# SystemStatusBoard.net
KiCad netlist of a schematic drawn in Altium Designer
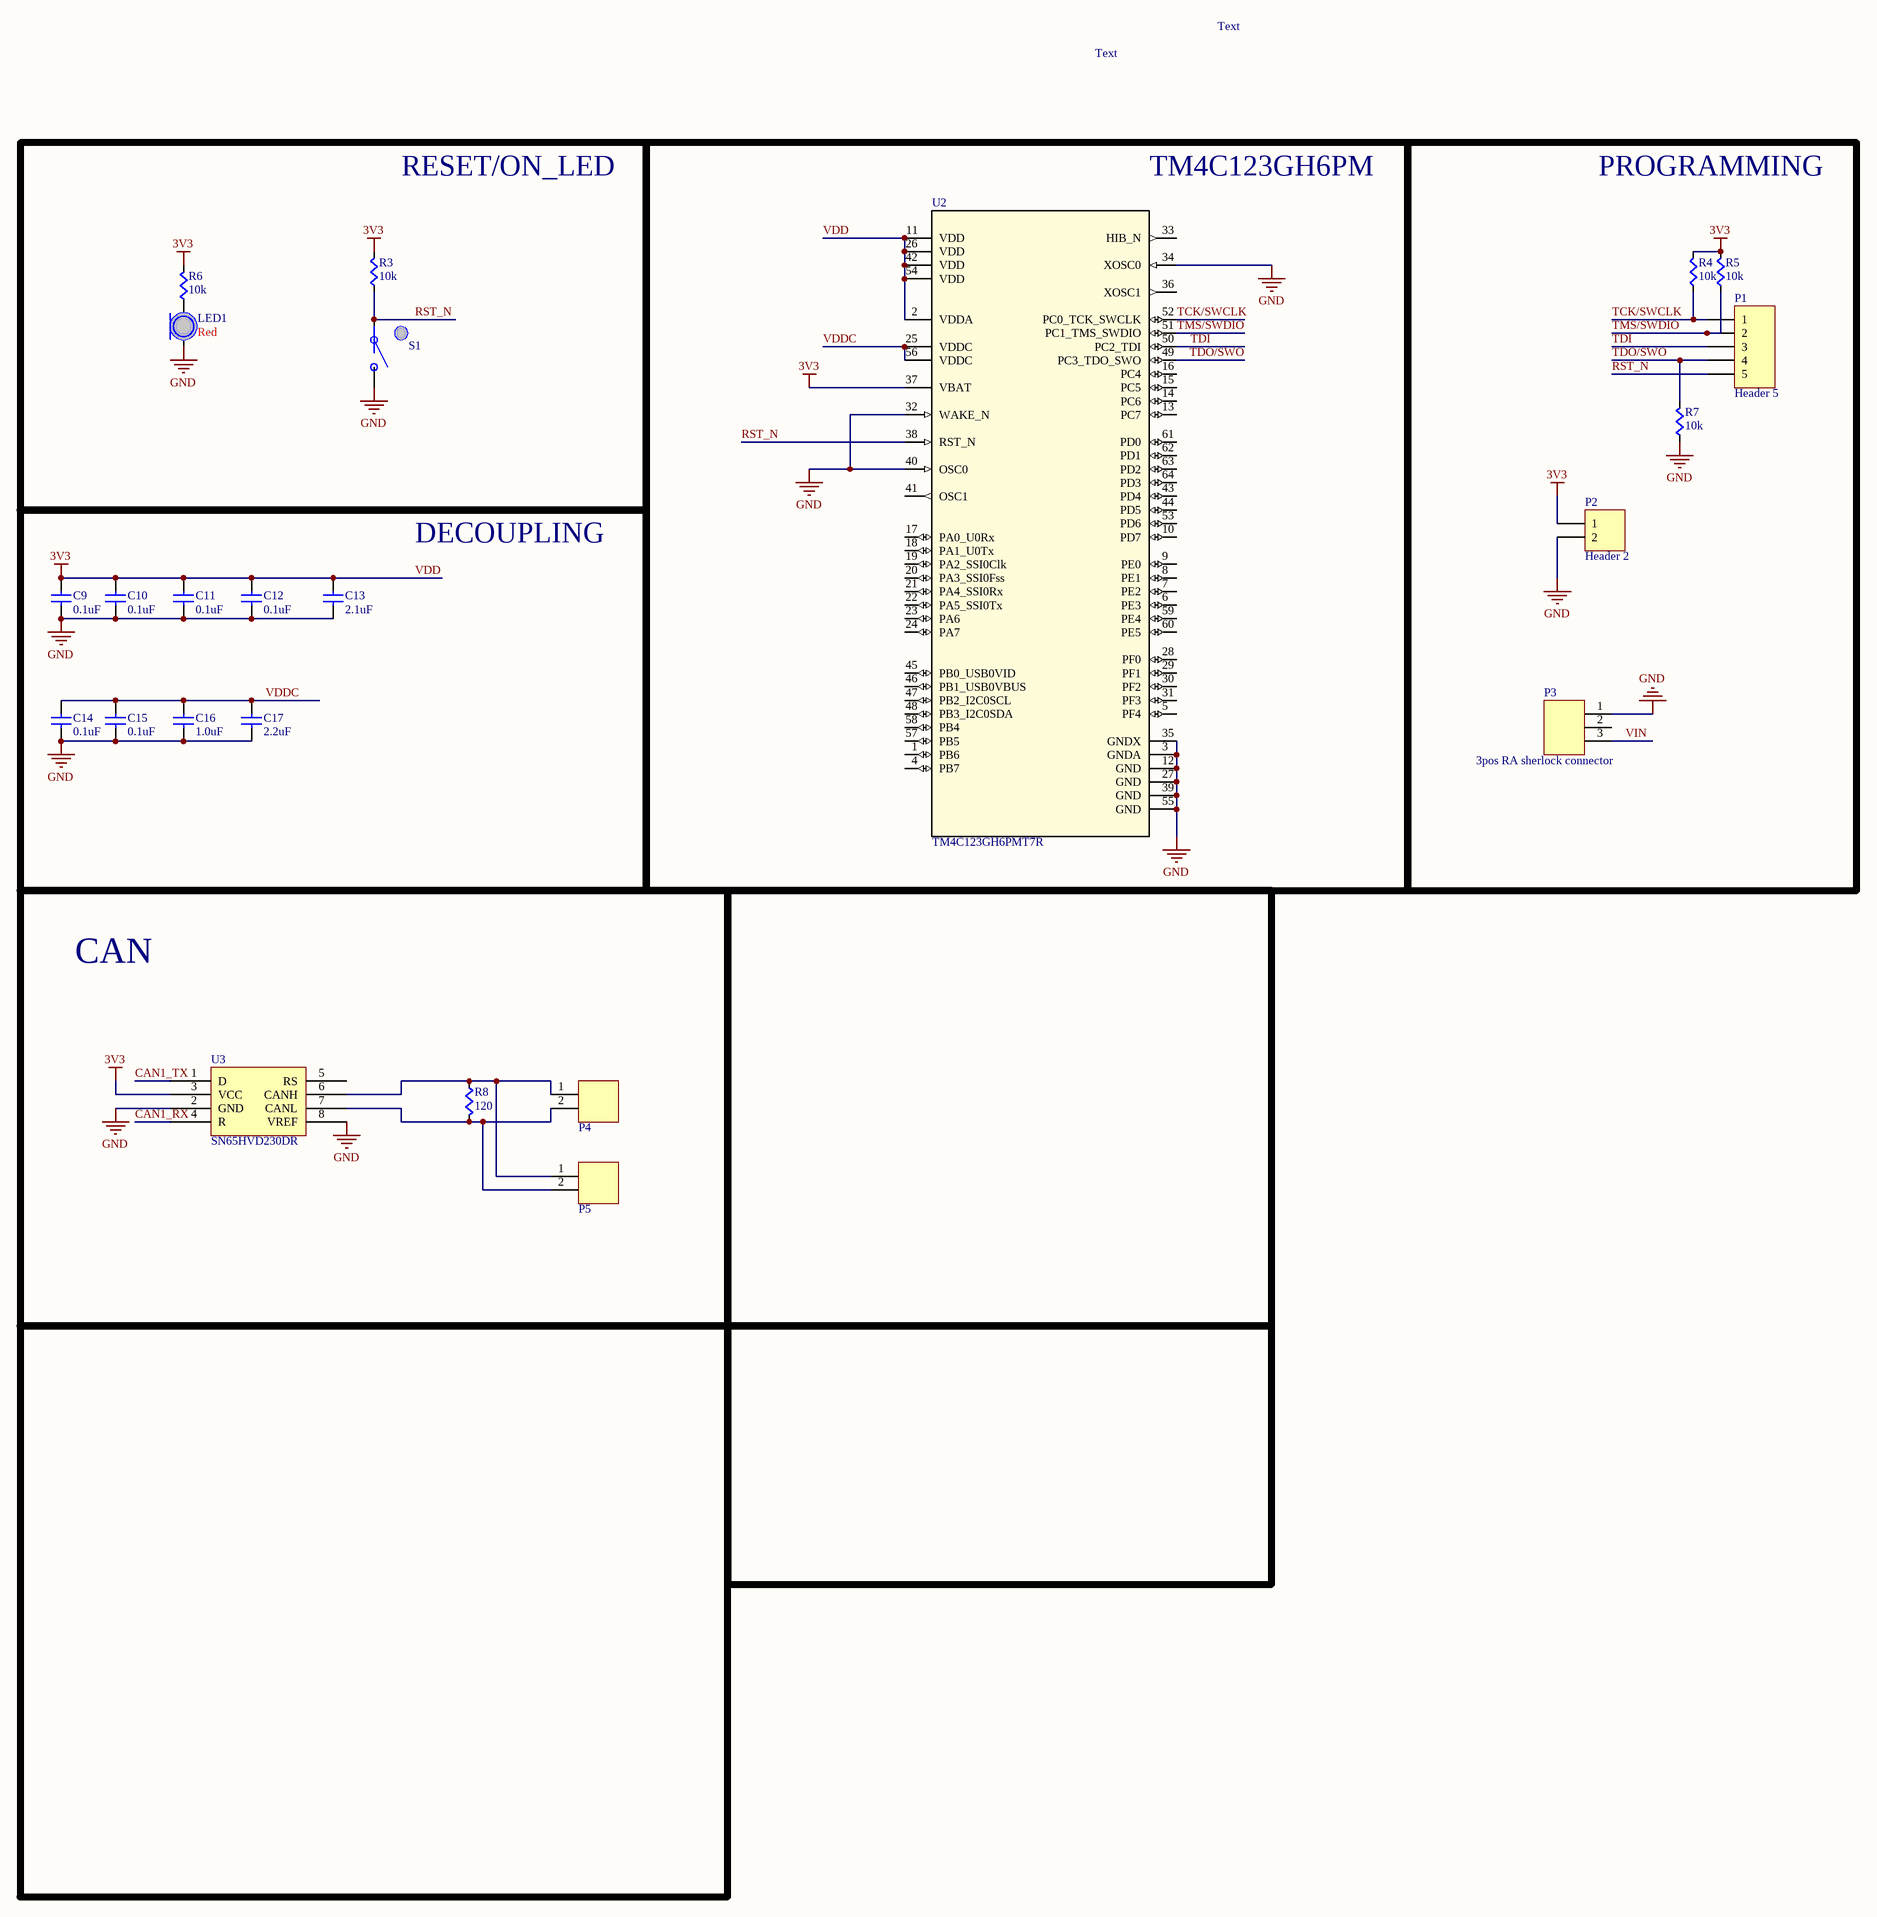
[diagram p0: SystemStatusBoard.SchDoc]

(export (version "E")
  (design (tool "Eeschema 10.0.6"))
  (components
    (comp (ref "C9")
      (value "0.1uF")
      (footprint "CAPC0603")
      (fields (field (name "Comment") "Cap"))
      (libsource (lib "SubjuGator8") (part "Cap"))
    )
    (comp (ref "C10")
      (value "0.1uF")
      (footprint "CAPC0603")
      (fields (field (name "Comment") "Cap"))
      (libsource (lib "SubjuGator8") (part "Cap"))
    )
    (comp (ref "C11")
      (value "0.1uF")
      (footprint "CAPC0603")
      (fields (field (name "Comment") "Cap"))
      (libsource (lib "SubjuGator8") (part "Cap"))
    )
    (comp (ref "C12")
      (value "0.1uF")
      (footprint "CAPC0603")
      (fields (field (name "Comment") "Cap"))
      (libsource (lib "SubjuGator8") (part "Cap"))
    )
    (comp (ref "C13")
      (value "2.1uF")
      (footprint "CAPC0603")
      (fields (field (name "Comment") "Cap"))
      (libsource (lib "SubjuGator8") (part "Cap"))
    )
    (comp (ref "C14")
      (value "0.1uF")
      (footprint "CAPC0603")
      (fields (field (name "Comment") "Cap"))
      (libsource (lib "SubjuGator8") (part "Cap"))
    )
    (comp (ref "C15")
      (value "0.1uF")
      (footprint "CAPC0603")
      (fields (field (name "Comment") "Cap"))
      (libsource (lib "SubjuGator8") (part "Cap"))
    )
    (comp (ref "C16")
      (value "1.0uF")
      (footprint "CAPC0603")
      (fields (field (name "Comment") "Cap"))
      (libsource (lib "SubjuGator8") (part "Cap"))
    )
    (comp (ref "C17")
      (value "2.2uF")
      (footprint "CAPC0603")
      (fields (field (name "Comment") "Cap"))
      (libsource (lib "SubjuGator8") (part "Cap"))
    )
    (comp (ref "LED1")
      (value "LED")
      (footprint "LED0603")
      (fields (field (name "COLOR") "Red"))
      (libsource (lib "SubjuGator8") (part "LED"))
    )
    (comp (ref "P1")
      (value "Header 5")
      (footprint "HDR1X5")
      (description "Header, 5-Pin")
      (fields (field (name "PUBLISHER") "Altium Limited"))
      (libsource (lib "Miscellaneous Connectors") (part "Header 5"))
    )
    (comp (ref "P2")
      (value "Header 2")
      (footprint "HDR1X2")
      (description "Header, 2-Pin")
      (fields (field (name "PUBLISHER") "Altium Limited"))
      (libsource (lib "Miscellaneous Connectors") (part "Header 2"))
    )
    (comp (ref "P3")
      (value "3pos RA sherlock connector")
      (footprint "MOLEX-HDR-1X3-SHERLOCK-RA")
      (description "Header, Molex, 2mm Pitch Sherlock Header, Single Row, Right Angle 3 Circuits, Length 3.3mm")
      (fields
        (field (name "MANUFACTURER PART NUMBER") "35363-0360")
        (field (name "MANUFACTURER") "Molex Connector Corporation")
      )
      (libsource (lib "Connectors") (part "MOLEX-HDR-1x3-SHERLOCK_RA"))
    )
    (comp (ref "P4")
      (value "2-pin Horz Sherlock")
      (footprint "MOLEX-HDR-1X2-SHERLOCK-HORZ")
      (fields
        (field (name "MANUFACTURER PART NUMBER") "0353630260")
        (field (name "MANUFACTURER") "Molex Inc")
      )
      (libsource (lib "SubjuGator8") (part "MOLEX-HDR-1x2-SHERLOCK_RA"))
    )
    (comp (ref "P5")
      (value "2-pin Horz Sherlock")
      (footprint "MOLEX-HDR-1X2-SHERLOCK-HORZ")
      (fields
        (field (name "MANUFACTURER PART NUMBER") "0353630260")
        (field (name "MANUFACTURER") "Molex Inc")
      )
      (libsource (lib "SubjuGator8") (part "MOLEX-HDR-1x2-SHERLOCK_RA"))
    )
    (comp (ref "R3")
      (value "10k")
      (footprint "RES0603")
      (fields (field (name "Comment") "Res"))
      (libsource (lib "SubjuGator8") (part "Res"))
    )
    (comp (ref "R4")
      (value "10k")
      (footprint "RES0603")
      (fields (field (name "Comment") "Res"))
      (libsource (lib "SubjuGator8") (part "Res"))
    )
    (comp (ref "R5")
      (value "10k")
      (footprint "RES0603")
      (fields (field (name "Comment") "Res"))
      (libsource (lib "SubjuGator8") (part "Res"))
    )
    (comp (ref "R6")
      (value "10k")
      (footprint "RES0603")
      (fields (field (name "Comment") "Res"))
      (libsource (lib "SubjuGator8") (part "Res"))
    )
    (comp (ref "R7")
      (value "10k")
      (footprint "RES0603")
      (fields (field (name "Comment") "Res"))
      (libsource (lib "SubjuGator8") (part "Res"))
    )
    (comp (ref "R8")
      (value "120")
      (footprint "RES0603")
      (fields (field (name "Comment") "Res"))
      (libsource (lib "SubjuGator8") (part "Res"))
    )
    (comp (ref "S1")
      (value "Button")
      (footprint "PTS645xxxxSMTR92")
      (description "SPST Button")
      (libsource (lib "SubjuGator8") (part "Button"))
    )
    (comp (ref "U2")
      (value "TM4C123GH6PMT7R")
      (footprint "PM0064A_N")
      (description "Imported")
      (fields
        (field (name "PARTNUMBER") "TM4C123GH6PMTR")
        (field (name "ALTERNATE_PARTNUMBER") "TM4C123GH6PMT")
      )
      (libsource (lib "TivaC") (part "TM4C123GH6PMT7R"))
    )
    (comp (ref "U3")
      (value "SN65HVD230DR")
      (footprint "SOIC-8pin")
      (description "IC TXRX CAN 1MBPS 3.3V 8SOIC")
      (libsource (lib "SubjuGator8") (part "SN65HVD230DR"))
    )
  )
  (nets
    (net (code "1") (name "/CAN1_RX") (class "Default")
      (node (ref "U3") (pin "4") (pinfunction "R_4") (pintype "passive"))
    )
    (net (code "2") (name "/CAN1_TX") (class "Default")
      (node (ref "U3") (pin "1") (pinfunction "D_1") (pintype "passive"))
    )
    (net (code "3") (name "/RST_N") (class "Default")
      (node (ref "P1") (pin "5") (pinfunction "5_5") (pintype "passive"))
      (node (ref "R3") (pin "2") (pinfunction "B_2") (pintype "passive"))
      (node (ref "S1") (pin "A") (pinfunction "A_A") (pintype "passive"))
      (node (ref "U2") (pin "38") (pinfunction "RST_N_38") (pintype "input"))
    )
    (net (code "4") (name "/TCK{slash}SWCLK") (class "Default")
      (node (ref "P1") (pin "1") (pinfunction "1_1") (pintype "passive"))
      (node (ref "R4") (pin "2") (pinfunction "B_2") (pintype "passive"))
      (node (ref "U2") (pin "52") (pinfunction "PC0_TCK_SWCLK_52") (pintype "bidirectional"))
    )
    (net (code "5") (name "/TDI") (class "Default")
      (node (ref "P1") (pin "3") (pinfunction "3_3") (pintype "passive"))
      (node (ref "U2") (pin "50") (pinfunction "PC2_TDI_50") (pintype "bidirectional"))
    )
    (net (code "6") (name "/TDO{slash}SWO") (class "Default")
      (node (ref "P1") (pin "4") (pinfunction "4_4") (pintype "passive"))
      (node (ref "R7") (pin "1") (pinfunction "A_1") (pintype "passive"))
      (node (ref "U2") (pin "49") (pinfunction "PC3_TDO_SWO_49") (pintype "bidirectional"))
    )
    (net (code "7") (name "/TMS{slash}SWDIO") (class "Default")
      (node (ref "P1") (pin "2") (pinfunction "2_2") (pintype "passive"))
      (node (ref "R5") (pin "2") (pinfunction "B_2") (pintype "passive"))
      (node (ref "U2") (pin "51") (pinfunction "PC1_TMS_SWDIO_51") (pintype "bidirectional"))
    )
    (net (code "8") (name "/VDDC") (class "Default")
      (node (ref "C14") (pin "1") (pinfunction "A_1") (pintype "passive"))
      (node (ref "C15") (pin "1") (pinfunction "A_1") (pintype "passive"))
      (node (ref "C16") (pin "1") (pinfunction "A_1") (pintype "passive"))
      (node (ref "C17") (pin "1") (pinfunction "A_1") (pintype "passive"))
      (node (ref "U2") (pin "25") (pinfunction "VDDC_25") (pintype "power_in"))
      (node (ref "U2") (pin "56") (pinfunction "VDDC_56") (pintype "power_in"))
    )
    (net (code "9") (name "/VIN") (class "Default")
      (node (ref "P3") (pin "3") (pinfunction "3_3") (pintype "passive"))
    )
    (net (code "10") (name "3V3") (class "Default")
      (node (ref "C10") (pin "1") (pinfunction "A_1") (pintype "passive"))
      (node (ref "C11") (pin "1") (pinfunction "A_1") (pintype "passive"))
      (node (ref "C12") (pin "1") (pinfunction "A_1") (pintype "passive"))
      (node (ref "C13") (pin "1") (pinfunction "A_1") (pintype "passive"))
      (node (ref "C9") (pin "1") (pinfunction "A_1") (pintype "passive"))
      (node (ref "P2") (pin "1") (pinfunction "1_1") (pintype "passive"))
      (node (ref "R3") (pin "1") (pinfunction "A_1") (pintype "passive"))
      (node (ref "R4") (pin "1") (pinfunction "A_1") (pintype "passive"))
      (node (ref "R5") (pin "1") (pinfunction "A_1") (pintype "passive"))
      (node (ref "R6") (pin "1") (pinfunction "A_1") (pintype "passive"))
      (node (ref "U2") (pin "11") (pinfunction "VDD_11") (pintype "power_in"))
      (node (ref "U2") (pin "2") (pinfunction "VDDA_2") (pintype "power_in"))
      (node (ref "U2") (pin "26") (pinfunction "VDD_26") (pintype "power_in"))
      (node (ref "U2") (pin "37") (pinfunction "VBAT_37") (pintype "power_in"))
      (node (ref "U2") (pin "42") (pinfunction "VDD_42") (pintype "power_in"))
      (node (ref "U2") (pin "54") (pinfunction "VDD_54") (pintype "power_in"))
      (node (ref "U3") (pin "3") (pinfunction "VCC_3") (pintype "passive"))
    )
    (net (code "11") (name "GND") (class "Default")
      (node (ref "C10") (pin "2") (pinfunction "B_2") (pintype "passive"))
      (node (ref "C11") (pin "2") (pinfunction "B_2") (pintype "passive"))
      (node (ref "C12") (pin "2") (pinfunction "B_2") (pintype "passive"))
      (node (ref "C13") (pin "2") (pinfunction "B_2") (pintype "passive"))
      (node (ref "C14") (pin "2") (pinfunction "B_2") (pintype "passive"))
      (node (ref "C15") (pin "2") (pinfunction "B_2") (pintype "passive"))
      (node (ref "C16") (pin "2") (pinfunction "B_2") (pintype "passive"))
      (node (ref "C17") (pin "2") (pinfunction "B_2") (pintype "passive"))
      (node (ref "C9") (pin "2") (pinfunction "B_2") (pintype "passive"))
      (node (ref "LED1") (pin "C") (pinfunction "C_C") (pintype "passive"))
      (node (ref "P2") (pin "2") (pinfunction "2_2") (pintype "passive"))
      (node (ref "P3") (pin "1") (pinfunction "1_1") (pintype "passive"))
      (node (ref "R7") (pin "2") (pinfunction "B_2") (pintype "passive"))
      (node (ref "S1") (pin "B") (pinfunction "B_B") (pintype "passive"))
      (node (ref "U2") (pin "12") (pinfunction "GND_12") (pintype "power_in"))
      (node (ref "U2") (pin "27") (pinfunction "GND_27") (pintype "power_in"))
      (node (ref "U2") (pin "3") (pinfunction "GNDA_3") (pintype "power_in"))
      (node (ref "U2") (pin "32") (pinfunction "WAKE_N_32") (pintype "input"))
      (node (ref "U2") (pin "34") (pinfunction "XOSC0_34") (pintype "input"))
      (node (ref "U2") (pin "35") (pinfunction "GNDX_35") (pintype "power_in"))
      (node (ref "U2") (pin "39") (pinfunction "GND_39") (pintype "power_in"))
      (node (ref "U2") (pin "40") (pinfunction "OSC0_40") (pintype "input"))
      (node (ref "U2") (pin "55") (pinfunction "GND_55") (pintype "power_in"))
      (node (ref "U3") (pin "2") (pinfunction "GND_2") (pintype "passive"))
      (node (ref "U3") (pin "8") (pinfunction "VREF_8") (pintype "passive"))
    )
    (net (code "12") (name "Net-(R6-B)") (class "Default")
      (node (ref "LED1") (pin "A") (pinfunction "A_A") (pintype "passive"))
      (node (ref "R6") (pin "2") (pinfunction "B_2") (pintype "passive"))
    )
    (net (code "13") (name "Net-(R8-A)") (class "Default")
      (node (ref "P4") (pin "2") (pinfunction "2_2") (pintype "passive"))
      (node (ref "P5") (pin "2") (pinfunction "2_2") (pintype "passive"))
      (node (ref "R8") (pin "1") (pinfunction "A_1") (pintype "passive"))
      (node (ref "U3") (pin "7") (pinfunction "CANL_7") (pintype "passive"))
    )
    (net (code "14") (name "Net-(R8-B)") (class "Default")
      (node (ref "P4") (pin "1") (pinfunction "1_1") (pintype "passive"))
      (node (ref "P5") (pin "1") (pinfunction "1_1") (pintype "passive"))
      (node (ref "R8") (pin "2") (pinfunction "B_2") (pintype "passive"))
      (node (ref "U3") (pin "6") (pinfunction "CANH_6") (pintype "passive"))
    )
    (net (code "15") (name "unconnected-(P3-Pad2)") (class "Default")
      (node (ref "P3") (pin "2") (pinfunction "2_2") (pintype "passive"))
    )
    (net (code "16") (name "unconnected-(U2-HIB_N-Pad33)") (class "Default")
      (node (ref "U2") (pin "33") (pinfunction "HIB_N_33") (pintype "output"))
    )
    (net (code "17") (name "unconnected-(U2-OSC1-Pad41)") (class "Default")
      (node (ref "U2") (pin "41") (pinfunction "OSC1_41") (pintype "output"))
    )
    (net (code "18") (name "unconnected-(U2-PA0_U0Rx-Pad17)") (class "Default")
      (node (ref "U2") (pin "17") (pinfunction "PA0_U0Rx_17") (pintype "bidirectional"))
    )
    (net (code "19") (name "unconnected-(U2-PA1_U0Tx-Pad18)") (class "Default")
      (node (ref "U2") (pin "18") (pinfunction "PA1_U0Tx_18") (pintype "bidirectional"))
    )
    (net (code "20") (name "unconnected-(U2-PA2_SSI0Clk-Pad19)") (class "Default")
      (node (ref "U2") (pin "19") (pinfunction "PA2_SSI0Clk_19") (pintype "bidirectional"))
    )
    (net (code "21") (name "unconnected-(U2-PA3_SSI0Fss-Pad20)") (class "Default")
      (node (ref "U2") (pin "20") (pinfunction "PA3_SSI0Fss_20") (pintype "bidirectional"))
    )
    (net (code "22") (name "unconnected-(U2-PA4_SSI0Rx-Pad21)") (class "Default")
      (node (ref "U2") (pin "21") (pinfunction "PA4_SSI0Rx_21") (pintype "bidirectional"))
    )
    (net (code "23") (name "unconnected-(U2-PA5_SSI0Tx-Pad22)") (class "Default")
      (node (ref "U2") (pin "22") (pinfunction "PA5_SSI0Tx_22") (pintype "bidirectional"))
    )
    (net (code "24") (name "unconnected-(U2-PA6-Pad23)") (class "Default")
      (node (ref "U2") (pin "23") (pinfunction "PA6_23") (pintype "bidirectional"))
    )
    (net (code "25") (name "unconnected-(U2-PA7-Pad24)") (class "Default")
      (node (ref "U2") (pin "24") (pinfunction "PA7_24") (pintype "bidirectional"))
    )
    (net (code "26") (name "unconnected-(U2-PB0_USB0VID-Pad45)") (class "Default")
      (node (ref "U2") (pin "45") (pinfunction "PB0_USB0VID_45") (pintype "bidirectional"))
    )
    (net (code "27") (name "unconnected-(U2-PB1_USB0VBUS-Pad46)") (class "Default")
      (node (ref "U2") (pin "46") (pinfunction "PB1_USB0VBUS_46") (pintype "bidirectional"))
    )
    (net (code "28") (name "unconnected-(U2-PB2_I2C0SCL-Pad47)") (class "Default")
      (node (ref "U2") (pin "47") (pinfunction "PB2_I2C0SCL_47") (pintype "bidirectional"))
    )
    (net (code "29") (name "unconnected-(U2-PB3_I2C0SDA-Pad48)") (class "Default")
      (node (ref "U2") (pin "48") (pinfunction "PB3_I2C0SDA_48") (pintype "bidirectional"))
    )
    (net (code "30") (name "unconnected-(U2-PB4-Pad58)") (class "Default")
      (node (ref "U2") (pin "58") (pinfunction "PB4_58") (pintype "bidirectional"))
    )
    (net (code "31") (name "unconnected-(U2-PB5-Pad57)") (class "Default")
      (node (ref "U2") (pin "57") (pinfunction "PB5_57") (pintype "bidirectional"))
    )
    (net (code "32") (name "unconnected-(U2-PB6-Pad1)") (class "Default")
      (node (ref "U2") (pin "1") (pinfunction "PB6_1") (pintype "bidirectional"))
    )
    (net (code "33") (name "unconnected-(U2-PB7-Pad4)") (class "Default")
      (node (ref "U2") (pin "4") (pinfunction "PB7_4") (pintype "bidirectional"))
    )
    (net (code "34") (name "unconnected-(U2-PC4-Pad16)") (class "Default")
      (node (ref "U2") (pin "16") (pinfunction "PC4_16") (pintype "bidirectional"))
    )
    (net (code "35") (name "unconnected-(U2-PC5-Pad15)") (class "Default")
      (node (ref "U2") (pin "15") (pinfunction "PC5_15") (pintype "bidirectional"))
    )
    (net (code "36") (name "unconnected-(U2-PC6-Pad14)") (class "Default")
      (node (ref "U2") (pin "14") (pinfunction "PC6_14") (pintype "bidirectional"))
    )
    (net (code "37") (name "unconnected-(U2-PC7-Pad13)") (class "Default")
      (node (ref "U2") (pin "13") (pinfunction "PC7_13") (pintype "bidirectional"))
    )
    (net (code "38") (name "unconnected-(U2-PD0-Pad61)") (class "Default")
      (node (ref "U2") (pin "61") (pinfunction "PD0_61") (pintype "bidirectional"))
    )
    (net (code "39") (name "unconnected-(U2-PD1-Pad62)") (class "Default")
      (node (ref "U2") (pin "62") (pinfunction "PD1_62") (pintype "bidirectional"))
    )
    (net (code "40") (name "unconnected-(U2-PD2-Pad63)") (class "Default")
      (node (ref "U2") (pin "63") (pinfunction "PD2_63") (pintype "bidirectional"))
    )
    (net (code "41") (name "unconnected-(U2-PD3-Pad64)") (class "Default")
      (node (ref "U2") (pin "64") (pinfunction "PD3_64") (pintype "bidirectional"))
    )
    (net (code "42") (name "unconnected-(U2-PD4-Pad43)") (class "Default")
      (node (ref "U2") (pin "43") (pinfunction "PD4_43") (pintype "bidirectional"))
    )
    (net (code "43") (name "unconnected-(U2-PD5-Pad44)") (class "Default")
      (node (ref "U2") (pin "44") (pinfunction "PD5_44") (pintype "bidirectional"))
    )
    (net (code "44") (name "unconnected-(U2-PD6-Pad53)") (class "Default")
      (node (ref "U2") (pin "53") (pinfunction "PD6_53") (pintype "bidirectional"))
    )
    (net (code "45") (name "unconnected-(U2-PD7-Pad10)") (class "Default")
      (node (ref "U2") (pin "10") (pinfunction "PD7_10") (pintype "bidirectional"))
    )
    (net (code "46") (name "unconnected-(U2-PE0-Pad9)") (class "Default")
      (node (ref "U2") (pin "9") (pinfunction "PE0_9") (pintype "bidirectional"))
    )
    (net (code "47") (name "unconnected-(U2-PE1-Pad8)") (class "Default")
      (node (ref "U2") (pin "8") (pinfunction "PE1_8") (pintype "bidirectional"))
    )
    (net (code "48") (name "unconnected-(U2-PE2-Pad7)") (class "Default")
      (node (ref "U2") (pin "7") (pinfunction "PE2_7") (pintype "bidirectional"))
    )
    (net (code "49") (name "unconnected-(U2-PE3-Pad6)") (class "Default")
      (node (ref "U2") (pin "6") (pinfunction "PE3_6") (pintype "bidirectional"))
    )
    (net (code "50") (name "unconnected-(U2-PE4-Pad59)") (class "Default")
      (node (ref "U2") (pin "59") (pinfunction "PE4_59") (pintype "bidirectional"))
    )
    (net (code "51") (name "unconnected-(U2-PE5-Pad60)") (class "Default")
      (node (ref "U2") (pin "60") (pinfunction "PE5_60") (pintype "bidirectional"))
    )
    (net (code "52") (name "unconnected-(U2-PF0-Pad28)") (class "Default")
      (node (ref "U2") (pin "28") (pinfunction "PF0_28") (pintype "bidirectional"))
    )
    (net (code "53") (name "unconnected-(U2-PF1-Pad29)") (class "Default")
      (node (ref "U2") (pin "29") (pinfunction "PF1_29") (pintype "bidirectional"))
    )
    (net (code "54") (name "unconnected-(U2-PF2-Pad30)") (class "Default")
      (node (ref "U2") (pin "30") (pinfunction "PF2_30") (pintype "bidirectional"))
    )
    (net (code "55") (name "unconnected-(U2-PF3-Pad31)") (class "Default")
      (node (ref "U2") (pin "31") (pinfunction "PF3_31") (pintype "bidirectional"))
    )
    (net (code "56") (name "unconnected-(U2-PF4-Pad5)") (class "Default")
      (node (ref "U2") (pin "5") (pinfunction "PF4_5") (pintype "bidirectional"))
    )
    (net (code "57") (name "unconnected-(U2-XOSC1-Pad36)") (class "Default")
      (node (ref "U2") (pin "36") (pinfunction "XOSC1_36") (pintype "output"))
    )
    (net (code "58") (name "unconnected-(U3-RS-Pad5)") (class "Default")
      (node (ref "U3") (pin "5") (pinfunction "RS_5") (pintype "passive"))
    )
  )
)
